# micron_P7.net
KiCad netlist of a schematic drawn in Altium Designer
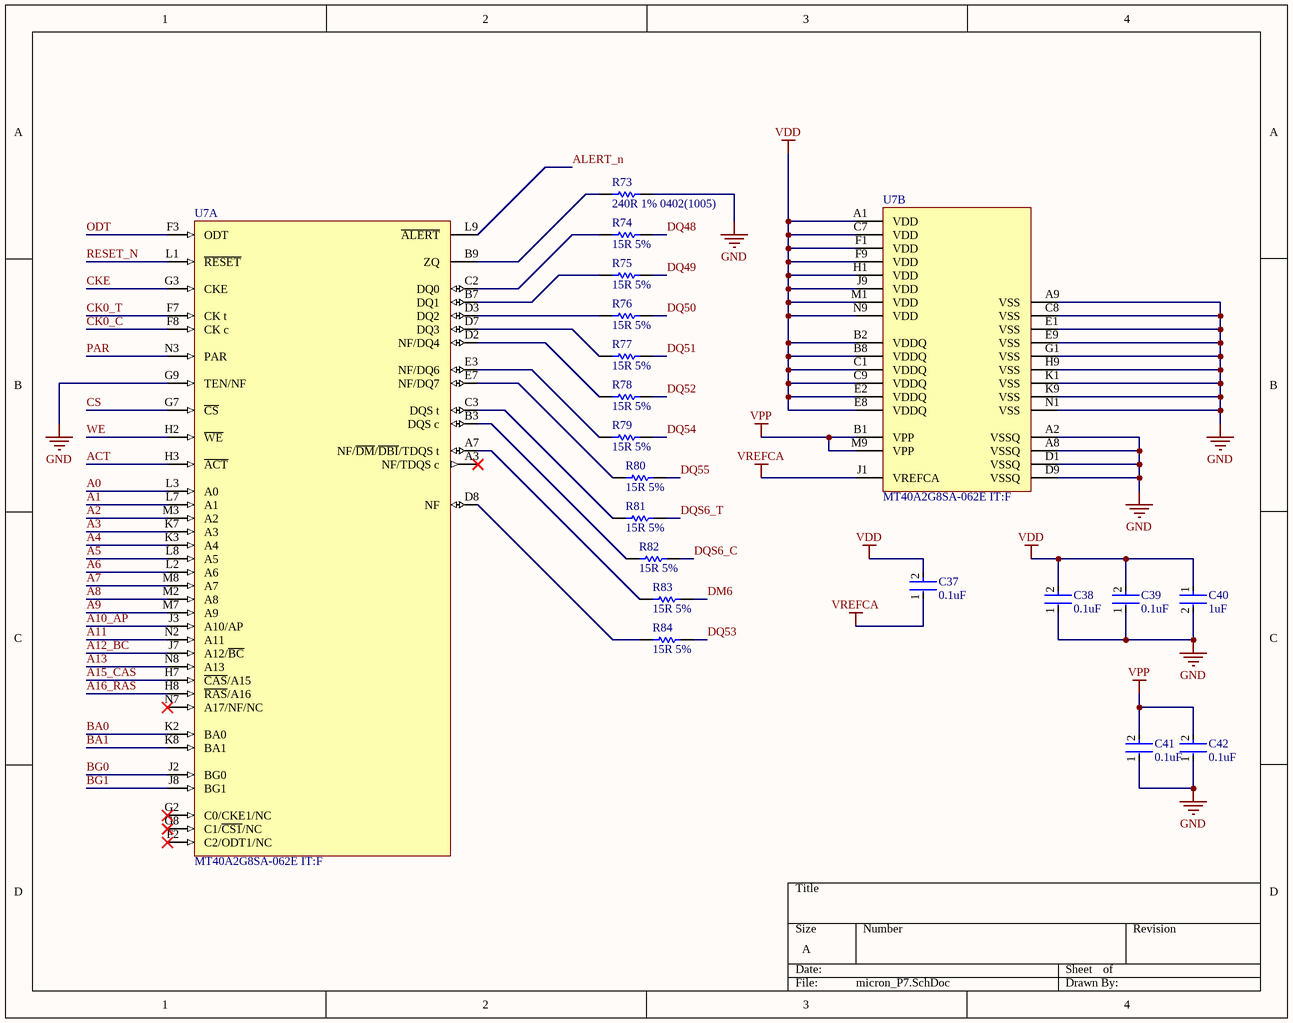
[diagram p0: micron_P7.SchDoc]

(export (version "E")
  (design (tool "Eeschema 10.0.6"))
  (components
    (comp (ref "C37")
      (value "0.1uF")
      (footprint "FP-GRM15-MFG")
      (description "CAP CER 0.1UF 16V X7R 0402")
      (fields (field (name "MANUFACTURER PART NUMBER") "GRM155R71C104KA88D") (field (name "TOLERANCE") "10%"))
      (libsource (lib "Altium Content Vault") (part "236180d848d6139a670b325ea6854c9"))
    )
    (comp (ref "C38")
      (value "0.1uF")
      (footprint "FP-GRM15-MFG")
      (description "CAP CER 0.1UF 16V X7R 0402")
      (fields (field (name "MANUFACTURER PART NUMBER") "GRM155R71C104KA88D") (field (name "TOLERANCE") "10%"))
      (libsource (lib "Altium Content Vault") (part "236180d848d6139a670b325ea6854c9"))
    )
    (comp (ref "C39")
      (value "0.1uF")
      (footprint "FP-GRM15-MFG")
      (description "CAP CER 0.1UF 16V X7R 0402")
      (fields (field (name "MANUFACTURER PART NUMBER") "GRM155R71C104KA88D") (field (name "TOLERANCE") "10%"))
      (libsource (lib "Altium Content Vault") (part "236180d848d6139a670b325ea6854c9"))
    )
    (comp (ref "C40")
      (value "1uF")
      (footprint "FP-CL511-IPC_C")
      (description "Cap Ceramic 1uF 10V X5R ±10% SMD 0402 +85°C Paper T/R")
      (fields (field (name "TOLERANCE") "10%"))
      (libsource (lib "Altium Content Vault") (part "b4654b650e69147ec39a6b967a45e02"))
    )
    (comp (ref "C41")
      (value "0.1uF")
      (footprint "FP-GRM15-MFG")
      (description "CAP CER 0.1UF 16V X7R 0402")
      (fields (field (name "MANUFACTURER PART NUMBER") "GRM155R71C104KA88D") (field (name "TOLERANCE") "10%"))
      (libsource (lib "Altium Content Vault") (part "236180d848d6139a670b325ea6854c9"))
    )
    (comp (ref "C42")
      (value "0.1uF")
      (footprint "FP-GRM15-MFG")
      (description "CAP CER 0.1UF 16V X7R 0402")
      (fields (field (name "MANUFACTURER PART NUMBER") "GRM155R71C104KA88D") (field (name "TOLERANCE") "10%"))
      (libsource (lib "Altium Content Vault") (part "236180d848d6139a670b325ea6854c9"))
    )
    (comp (ref "R73")
      (value "240R 1% 0402(1005)")
      (footprint "RESC0402(1005)_L")
      (description "240R 0.063W 1% 0402 (1005 Metric)  SMD")
      (fields (field (name "POWER") "0.063 W") (field (name "TOLERANCE") "1 %"))
      (libsource (lib "Altium Content Vault") (part "RES"))
    )
    (comp (ref "R74")
      (value "15R 5%")
      (footprint "RESC1005X40X25LL05T10")
      (fields (field (name "MANUFACTURER") "Yageo / Phycomp") (field (name "PART NUMBER") "RC0402FR-0715RL"))
      (libsource (lib "Altium Content Vault") (part "RES"))
    )
    (comp (ref "R75")
      (value "15R 5%")
      (footprint "RESC1005X40X25LL05T10")
      (fields (field (name "MANUFACTURER") "Yageo / Phycomp") (field (name "PART NUMBER") "RC0402FR-0715RL"))
      (libsource (lib "Altium Content Vault") (part "RES"))
    )
    (comp (ref "R76")
      (value "15R 5%")
      (footprint "RESC1005X40X25LL05T10")
      (fields (field (name "MANUFACTURER") "Yageo / Phycomp") (field (name "PART NUMBER") "RC0402FR-0715RL"))
      (libsource (lib "Altium Content Vault") (part "RES"))
    )
    (comp (ref "R77")
      (value "15R 5%")
      (footprint "RESC1005X40X25LL05T10")
      (fields (field (name "MANUFACTURER") "Yageo / Phycomp") (field (name "PART NUMBER") "RC0402FR-0715RL"))
      (libsource (lib "Altium Content Vault") (part "RES"))
    )
    (comp (ref "R78")
      (value "15R 5%")
      (footprint "RESC1005X40X25LL05T10")
      (fields (field (name "MANUFACTURER") "Yageo / Phycomp") (field (name "PART NUMBER") "RC0402FR-0715RL"))
      (libsource (lib "Altium Content Vault") (part "RES"))
    )
    (comp (ref "R79")
      (value "15R 5%")
      (footprint "RESC1005X40X25LL05T10")
      (fields (field (name "MANUFACTURER") "Yageo / Phycomp") (field (name "PART NUMBER") "RC0402FR-0715RL"))
      (libsource (lib "Altium Content Vault") (part "RES"))
    )
    (comp (ref "R80")
      (value "15R 5%")
      (footprint "RESC1005X40X25LL05T10")
      (fields (field (name "MANUFACTURER") "Yageo / Phycomp") (field (name "PART NUMBER") "RC0402FR-0715RL"))
      (libsource (lib "Altium Content Vault") (part "RES"))
    )
    (comp (ref "R81")
      (value "15R 5%")
      (footprint "RESC1005X40X25LL05T10")
      (fields (field (name "MANUFACTURER") "Yageo / Phycomp") (field (name "PART NUMBER") "RC0402FR-0715RL"))
      (libsource (lib "Altium Content Vault") (part "RES"))
    )
    (comp (ref "R82")
      (value "15R 5%")
      (footprint "RESC1005X40X25LL05T10")
      (fields (field (name "MANUFACTURER") "Yageo / Phycomp") (field (name "PART NUMBER") "RC0402FR-0715RL"))
      (libsource (lib "Altium Content Vault") (part "RES"))
    )
    (comp (ref "R83")
      (value "15R 5%")
      (footprint "RESC1005X40X25LL05T10")
      (fields (field (name "MANUFACTURER") "Yageo / Phycomp") (field (name "PART NUMBER") "RC0402FR-0715RL"))
      (libsource (lib "Altium Content Vault") (part "RES"))
    )
    (comp (ref "R84")
      (value "15R 5%")
      (footprint "RESC1005X40X25LL05T10")
      (fields (field (name "MANUFACTURER") "Yageo / Phycomp") (field (name "PART NUMBER") "RC0402FR-0715RL"))
      (libsource (lib "Altium Content Vault") (part "RES"))
    )
    (comp (ref "U7")
      (value "MT40A2G8SA-062E IT:F")
      (footprint "SA_MFG")
      (description "DRAMChip DDR4 SDRAM 16Gbit 2Gx8 1.2V 78-Pin FBGA Tray")
      (libsource (lib "Altium Content Vault") (part "d28cb998757b614ee3280f10a38a3b1"))
    )
  )
  (nets
    (net (code "1") (name "/A0") (class "Default")
      (node (ref "U7") (pin "L3") (pinfunction "A0_L3") (pintype "input"))
    )
    (net (code "2") (name "/A1") (class "Default")
      (node (ref "U7") (pin "L7") (pinfunction "A1_L7") (pintype "input"))
    )
    (net (code "3") (name "/A2") (class "Default")
      (node (ref "U7") (pin "M3") (pinfunction "A2_M3") (pintype "input"))
    )
    (net (code "4") (name "/A3") (class "Default")
      (node (ref "U7") (pin "K7") (pinfunction "A3_K7") (pintype "input"))
    )
    (net (code "5") (name "/A4") (class "Default")
      (node (ref "U7") (pin "K3") (pinfunction "A4_K3") (pintype "input"))
    )
    (net (code "6") (name "/A5") (class "Default")
      (node (ref "U7") (pin "L8") (pinfunction "A5_L8") (pintype "input"))
    )
    (net (code "7") (name "/A6") (class "Default")
      (node (ref "U7") (pin "L2") (pinfunction "A6_L2") (pintype "input"))
    )
    (net (code "8") (name "/A7") (class "Default")
      (node (ref "U7") (pin "M8") (pinfunction "A7_M8") (pintype "input"))
    )
    (net (code "9") (name "/A8") (class "Default")
      (node (ref "U7") (pin "M2") (pinfunction "A8_M2") (pintype "input"))
    )
    (net (code "10") (name "/A9") (class "Default")
      (node (ref "U7") (pin "M7") (pinfunction "A9_M7") (pintype "input"))
    )
    (net (code "11") (name "/A10_AP") (class "Default")
      (node (ref "U7") (pin "J3") (pinfunction "A10/AP_J3") (pintype "input"))
    )
    (net (code "12") (name "/A11") (class "Default")
      (node (ref "U7") (pin "N2") (pinfunction "A11_N2") (pintype "input"))
    )
    (net (code "13") (name "/A12_BC") (class "Default")
      (node (ref "U7") (pin "J7") (pinfunction "A12/~{BC}_J7") (pintype "input"))
    )
    (net (code "14") (name "/A13") (class "Default")
      (node (ref "U7") (pin "N8") (pinfunction "A13_N8") (pintype "input"))
    )
    (net (code "15") (name "/A15_CAS") (class "Default")
      (node (ref "U7") (pin "H7") (pinfunction "~{CAS}/A15_H7") (pintype "input"))
    )
    (net (code "16") (name "/A16_RAS") (class "Default")
      (node (ref "U7") (pin "H8") (pinfunction "~{RAS}/A16_H8") (pintype "input"))
    )
    (net (code "17") (name "/ACT") (class "Default")
      (node (ref "U7") (pin "H3") (pinfunction "~{ACT}_H3") (pintype "input"))
    )
    (net (code "18") (name "/ALERT_n") (class "Default")
      (node (ref "U7") (pin "L9") (pinfunction "~{ALERT}_L9") (pintype "open_collector"))
    )
    (net (code "19") (name "/BA0") (class "Default")
      (node (ref "U7") (pin "K2") (pinfunction "BA0_K2") (pintype "input"))
    )
    (net (code "20") (name "/BA1") (class "Default")
      (node (ref "U7") (pin "K8") (pinfunction "BA1_K8") (pintype "input"))
    )
    (net (code "21") (name "/BG0") (class "Default")
      (node (ref "U7") (pin "J2") (pinfunction "BG0_J2") (pintype "input"))
    )
    (net (code "22") (name "/BG1") (class "Default")
      (node (ref "U7") (pin "J8") (pinfunction "BG1_J8") (pintype "input"))
    )
    (net (code "23") (name "/CK0_C") (class "Default")
      (node (ref "U7") (pin "F8") (pinfunction "CK_c_F8") (pintype "input"))
    )
    (net (code "24") (name "/CK0_T") (class "Default")
      (node (ref "U7") (pin "F7") (pinfunction "CK_t_F7") (pintype "input"))
    )
    (net (code "25") (name "/CKE") (class "Default")
      (node (ref "U7") (pin "G3") (pinfunction "CKE_G3") (pintype "input"))
    )
    (net (code "26") (name "/CS") (class "Default")
      (node (ref "U7") (pin "G7") (pinfunction "~{CS}_G7") (pintype "input"))
    )
    (net (code "27") (name "/DM6") (class "Default")
      (node (ref "R83") (pin "2") (pinfunction "2_2") (pintype "passive"))
    )
    (net (code "28") (name "/DQ48") (class "Default")
      (node (ref "R74") (pin "2") (pinfunction "2_2") (pintype "passive"))
    )
    (net (code "29") (name "/DQ49") (class "Default")
      (node (ref "R75") (pin "2") (pinfunction "2_2") (pintype "passive"))
    )
    (net (code "30") (name "/DQ50") (class "Default")
      (node (ref "R76") (pin "2") (pinfunction "2_2") (pintype "passive"))
    )
    (net (code "31") (name "/DQ51") (class "Default")
      (node (ref "R77") (pin "2") (pinfunction "2_2") (pintype "passive"))
    )
    (net (code "32") (name "/DQ52") (class "Default")
      (node (ref "R78") (pin "2") (pinfunction "2_2") (pintype "passive"))
    )
    (net (code "33") (name "/DQ53") (class "Default")
      (node (ref "R84") (pin "2") (pinfunction "2_2") (pintype "passive"))
    )
    (net (code "34") (name "/DQ54") (class "Default")
      (node (ref "R79") (pin "2") (pinfunction "2_2") (pintype "passive"))
    )
    (net (code "35") (name "/DQ55") (class "Default")
      (node (ref "R80") (pin "2") (pinfunction "2_2") (pintype "passive"))
    )
    (net (code "36") (name "/DQS6_C") (class "Default")
      (node (ref "R82") (pin "2") (pinfunction "2_2") (pintype "passive"))
    )
    (net (code "37") (name "/DQS6_T") (class "Default")
      (node (ref "R81") (pin "2") (pinfunction "2_2") (pintype "passive"))
    )
    (net (code "38") (name "/ODT") (class "Default")
      (node (ref "U7") (pin "F3") (pinfunction "ODT_F3") (pintype "input"))
    )
    (net (code "39") (name "/PAR") (class "Default")
      (node (ref "U7") (pin "N3") (pinfunction "PAR_N3") (pintype "input"))
    )
    (net (code "40") (name "/RESET_N") (class "Default")
      (node (ref "U7") (pin "L1") (pinfunction "~{RESET}_L1") (pintype "input"))
    )
    (net (code "41") (name "/WE") (class "Default")
      (node (ref "U7") (pin "H2") (pinfunction "~{WE}_H2") (pintype "input"))
    )
    (net (code "42") (name "GND") (class "Default")
      (node (ref "C38") (pin "1") (pinfunction "1_1") (pintype "passive"))
      (node (ref "C39") (pin "1") (pinfunction "1_1") (pintype "passive"))
      (node (ref "C40") (pin "2") (pinfunction "2_2") (pintype "passive"))
      (node (ref "C41") (pin "1") (pinfunction "1_1") (pintype "passive"))
      (node (ref "C42") (pin "1") (pinfunction "1_1") (pintype "passive"))
      (node (ref "R73") (pin "2") (pinfunction "2_2") (pintype "passive"))
      (node (ref "U7") (pin "A2") (pinfunction "VSSQ_A2") (pintype "power_in"))
      (node (ref "U7") (pin "A8") (pinfunction "VSSQ_A8") (pintype "power_in"))
      (node (ref "U7") (pin "A9") (pinfunction "VSS_A9") (pintype "power_in"))
      (node (ref "U7") (pin "C8") (pinfunction "VSS_C8") (pintype "power_in"))
      (node (ref "U7") (pin "D1") (pinfunction "VSSQ_D1") (pintype "power_in"))
      (node (ref "U7") (pin "D9") (pinfunction "VSSQ_D9") (pintype "power_in"))
      (node (ref "U7") (pin "E1") (pinfunction "VSS_E1") (pintype "power_in"))
      (node (ref "U7") (pin "E9") (pinfunction "VSS_E9") (pintype "power_in"))
      (node (ref "U7") (pin "G1") (pinfunction "VSS_G1") (pintype "power_in"))
      (node (ref "U7") (pin "G9") (pinfunction "TEN/NF_G9") (pintype "input"))
      (node (ref "U7") (pin "H9") (pinfunction "VSS_H9") (pintype "power_in"))
      (node (ref "U7") (pin "K1") (pinfunction "VSS_K1") (pintype "power_in"))
      (node (ref "U7") (pin "K9") (pinfunction "VSS_K9") (pintype "power_in"))
      (node (ref "U7") (pin "N1") (pinfunction "VSS_N1") (pintype "power_in"))
    )
    (net (code "43") (name "Net-(U7A-DQ0)") (class "Default")
      (node (ref "R74") (pin "1") (pinfunction "1_1") (pintype "passive"))
      (node (ref "U7") (pin "C2") (pinfunction "DQ0_C2") (pintype "bidirectional"))
    )
    (net (code "44") (name "Net-(U7A-DQ1)") (class "Default")
      (node (ref "R75") (pin "1") (pinfunction "1_1") (pintype "passive"))
      (node (ref "U7") (pin "B7") (pinfunction "DQ1_B7") (pintype "bidirectional"))
    )
    (net (code "45") (name "Net-(U7A-DQ2)") (class "Default")
      (node (ref "R76") (pin "1") (pinfunction "1_1") (pintype "passive"))
      (node (ref "U7") (pin "D3") (pinfunction "DQ2_D3") (pintype "bidirectional"))
    )
    (net (code "46") (name "Net-(U7A-DQ3)") (class "Default")
      (node (ref "R77") (pin "1") (pinfunction "1_1") (pintype "passive"))
      (node (ref "U7") (pin "D7") (pinfunction "DQ3_D7") (pintype "bidirectional"))
    )
    (net (code "47") (name "Net-(U7A-DQS_c)") (class "Default")
      (node (ref "R82") (pin "1") (pinfunction "1_1") (pintype "passive"))
      (node (ref "U7") (pin "B3") (pinfunction "DQS_c_B3") (pintype "bidirectional"))
    )
    (net (code "48") (name "Net-(U7A-DQS_t)") (class "Default")
      (node (ref "R81") (pin "1") (pinfunction "1_1") (pintype "passive"))
      (node (ref "U7") (pin "C3") (pinfunction "DQS_t_C3") (pintype "bidirectional"))
    )
    (net (code "49") (name "Net-(U7A-NF)") (class "Default")
      (node (ref "R84") (pin "1") (pinfunction "1_1") (pintype "passive"))
      (node (ref "U7") (pin "D8") (pinfunction "NF_D8") (pintype "bidirectional"))
    )
    (net (code "50") (name "Net-(U7A-NF{slash}DQ4)") (class "Default")
      (node (ref "R78") (pin "1") (pinfunction "1_1") (pintype "passive"))
      (node (ref "U7") (pin "D2") (pinfunction "NF/DQ4_D2") (pintype "bidirectional"))
    )
    (net (code "51") (name "Net-(U7A-NF{slash}DQ6)") (class "Default")
      (node (ref "R79") (pin "1") (pinfunction "1_1") (pintype "passive"))
      (node (ref "U7") (pin "E3") (pinfunction "NF/DQ6_E3") (pintype "bidirectional"))
    )
    (net (code "52") (name "Net-(U7A-NF{slash}DQ7)") (class "Default")
      (node (ref "R80") (pin "1") (pinfunction "1_1") (pintype "passive"))
      (node (ref "U7") (pin "E7") (pinfunction "NF/DQ7_E7") (pintype "bidirectional"))
    )
    (net (code "53") (name "Net-(U7A-NF{slash}~{DM}{slash}~{DBI}{slash}TDQS_t)") (class "Default")
      (node (ref "R83") (pin "1") (pinfunction "1_1") (pintype "passive"))
      (node (ref "U7") (pin "A7") (pinfunction "NF/~{DM}/~{DBI}/TDQS_t_A7") (pintype "bidirectional"))
    )
    (net (code "54") (name "Net-(U7A-ZQ)") (class "Default")
      (node (ref "R73") (pin "1") (pinfunction "1_1") (pintype "passive"))
      (node (ref "U7") (pin "B9") (pinfunction "ZQ_B9") (pintype "passive"))
    )
    (net (code "55") (name "VDD") (class "Default")
      (node (ref "C37") (pin "2") (pinfunction "2_2") (pintype "passive"))
      (node (ref "C38") (pin "2") (pinfunction "2_2") (pintype "passive"))
      (node (ref "C39") (pin "2") (pinfunction "2_2") (pintype "passive"))
      (node (ref "C40") (pin "1") (pinfunction "1_1") (pintype "passive"))
      (node (ref "U7") (pin "A1") (pinfunction "VDD_A1") (pintype "power_in"))
      (node (ref "U7") (pin "B2") (pinfunction "VDDQ_B2") (pintype "power_in"))
      (node (ref "U7") (pin "B8") (pinfunction "VDDQ_B8") (pintype "power_in"))
      (node (ref "U7") (pin "C1") (pinfunction "VDDQ_C1") (pintype "power_in"))
      (node (ref "U7") (pin "C7") (pinfunction "VDD_C7") (pintype "power_in"))
      (node (ref "U7") (pin "C9") (pinfunction "VDDQ_C9") (pintype "power_in"))
      (node (ref "U7") (pin "E2") (pinfunction "VDDQ_E2") (pintype "power_in"))
      (node (ref "U7") (pin "E8") (pinfunction "VDDQ_E8") (pintype "power_in"))
      (node (ref "U7") (pin "F1") (pinfunction "VDD_F1") (pintype "power_in"))
      (node (ref "U7") (pin "F9") (pinfunction "VDD_F9") (pintype "power_in"))
      (node (ref "U7") (pin "H1") (pinfunction "VDD_H1") (pintype "power_in"))
      (node (ref "U7") (pin "J9") (pinfunction "VDD_J9") (pintype "power_in"))
      (node (ref "U7") (pin "M1") (pinfunction "VDD_M1") (pintype "power_in"))
      (node (ref "U7") (pin "N9") (pinfunction "VDD_N9") (pintype "power_in"))
    )
    (net (code "56") (name "VPP") (class "Default")
      (node (ref "C41") (pin "2") (pinfunction "2_2") (pintype "passive"))
      (node (ref "C42") (pin "2") (pinfunction "2_2") (pintype "passive"))
      (node (ref "U7") (pin "B1") (pinfunction "VPP_B1") (pintype "power_in"))
      (node (ref "U7") (pin "M9") (pinfunction "VPP_M9") (pintype "power_in"))
    )
    (net (code "57") (name "VREFCA") (class "Default")
      (node (ref "C37") (pin "1") (pinfunction "1_1") (pintype "passive"))
      (node (ref "U7") (pin "J1") (pinfunction "VREFCA_J1") (pintype "power_in"))
    )
    (net (code "58") (name "unconnected-(U7A-A17{slash}NF{slash}NC-PadN7)") (class "Default")
      (node (ref "U7") (pin "N7") (pinfunction "A17/NF/NC_N7") (pintype "input+no_connect"))
    )
    (net (code "59") (name "unconnected-(U7A-C0{slash}CKE1{slash}NC-PadG2)") (class "Default")
      (node (ref "U7") (pin "G2") (pinfunction "C0/CKE1/NC_G2") (pintype "input+no_connect"))
    )
    (net (code "60") (name "unconnected-(U7A-C1{slash}~{CS1}{slash}NC-PadG8)") (class "Default")
      (node (ref "U7") (pin "G8") (pinfunction "C1/~{CS1}/NC_G8") (pintype "input+no_connect"))
    )
    (net (code "61") (name "unconnected-(U7A-C2{slash}ODT1{slash}NC-PadF2)") (class "Default")
      (node (ref "U7") (pin "F2") (pinfunction "C2/ODT1/NC_F2") (pintype "input+no_connect"))
    )
    (net (code "62") (name "unconnected-(U7A-NF{slash}TDQS_c-PadA3)") (class "Default")
      (node (ref "U7") (pin "A3") (pinfunction "NF/TDQS_c_A3") (pintype "output+no_connect"))
    )
  )
)
